# tx.net
KiCad netlist of a schematic drawn in EAGLE
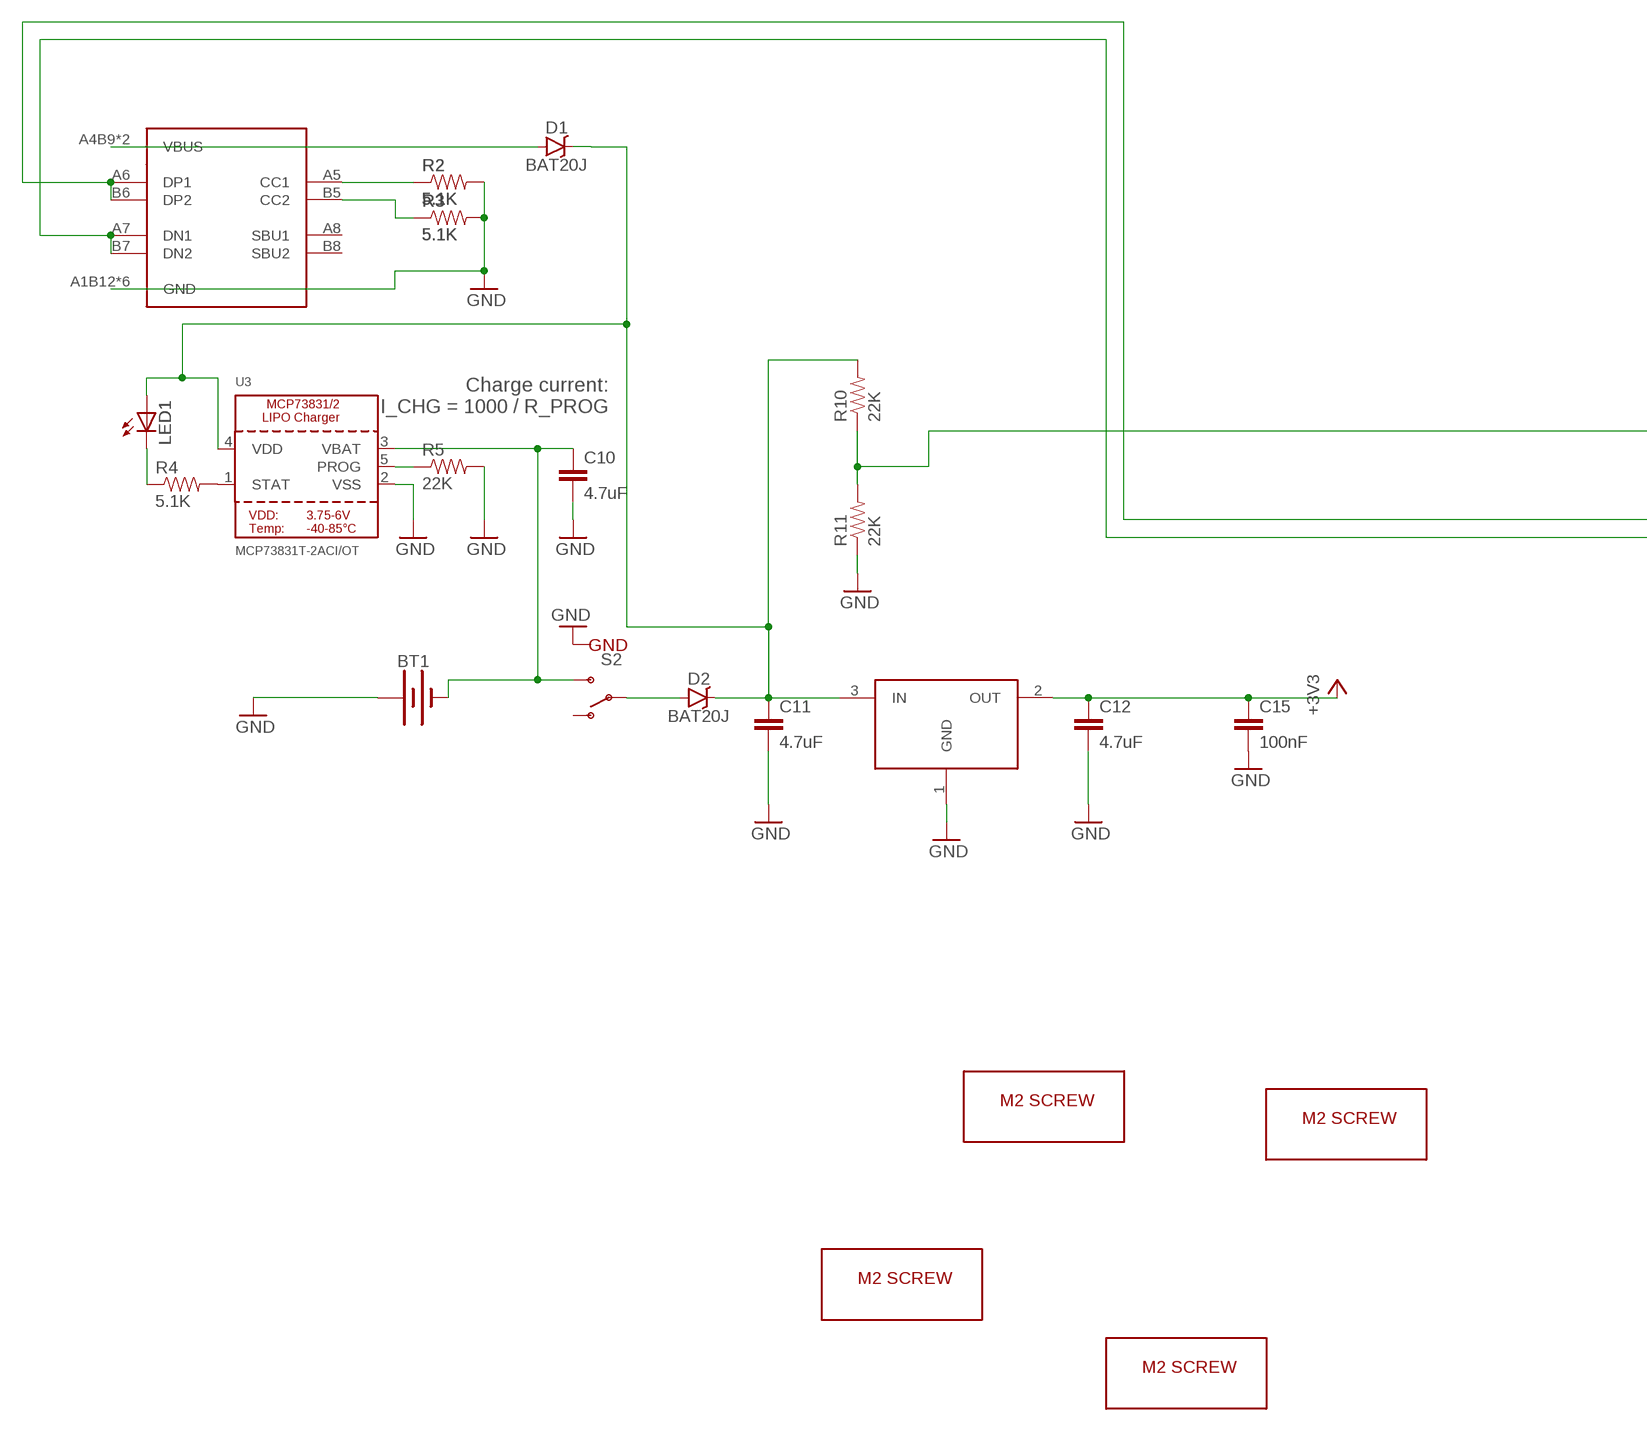
[diagram p0: schematic, sheet 1, part 1 of 2]
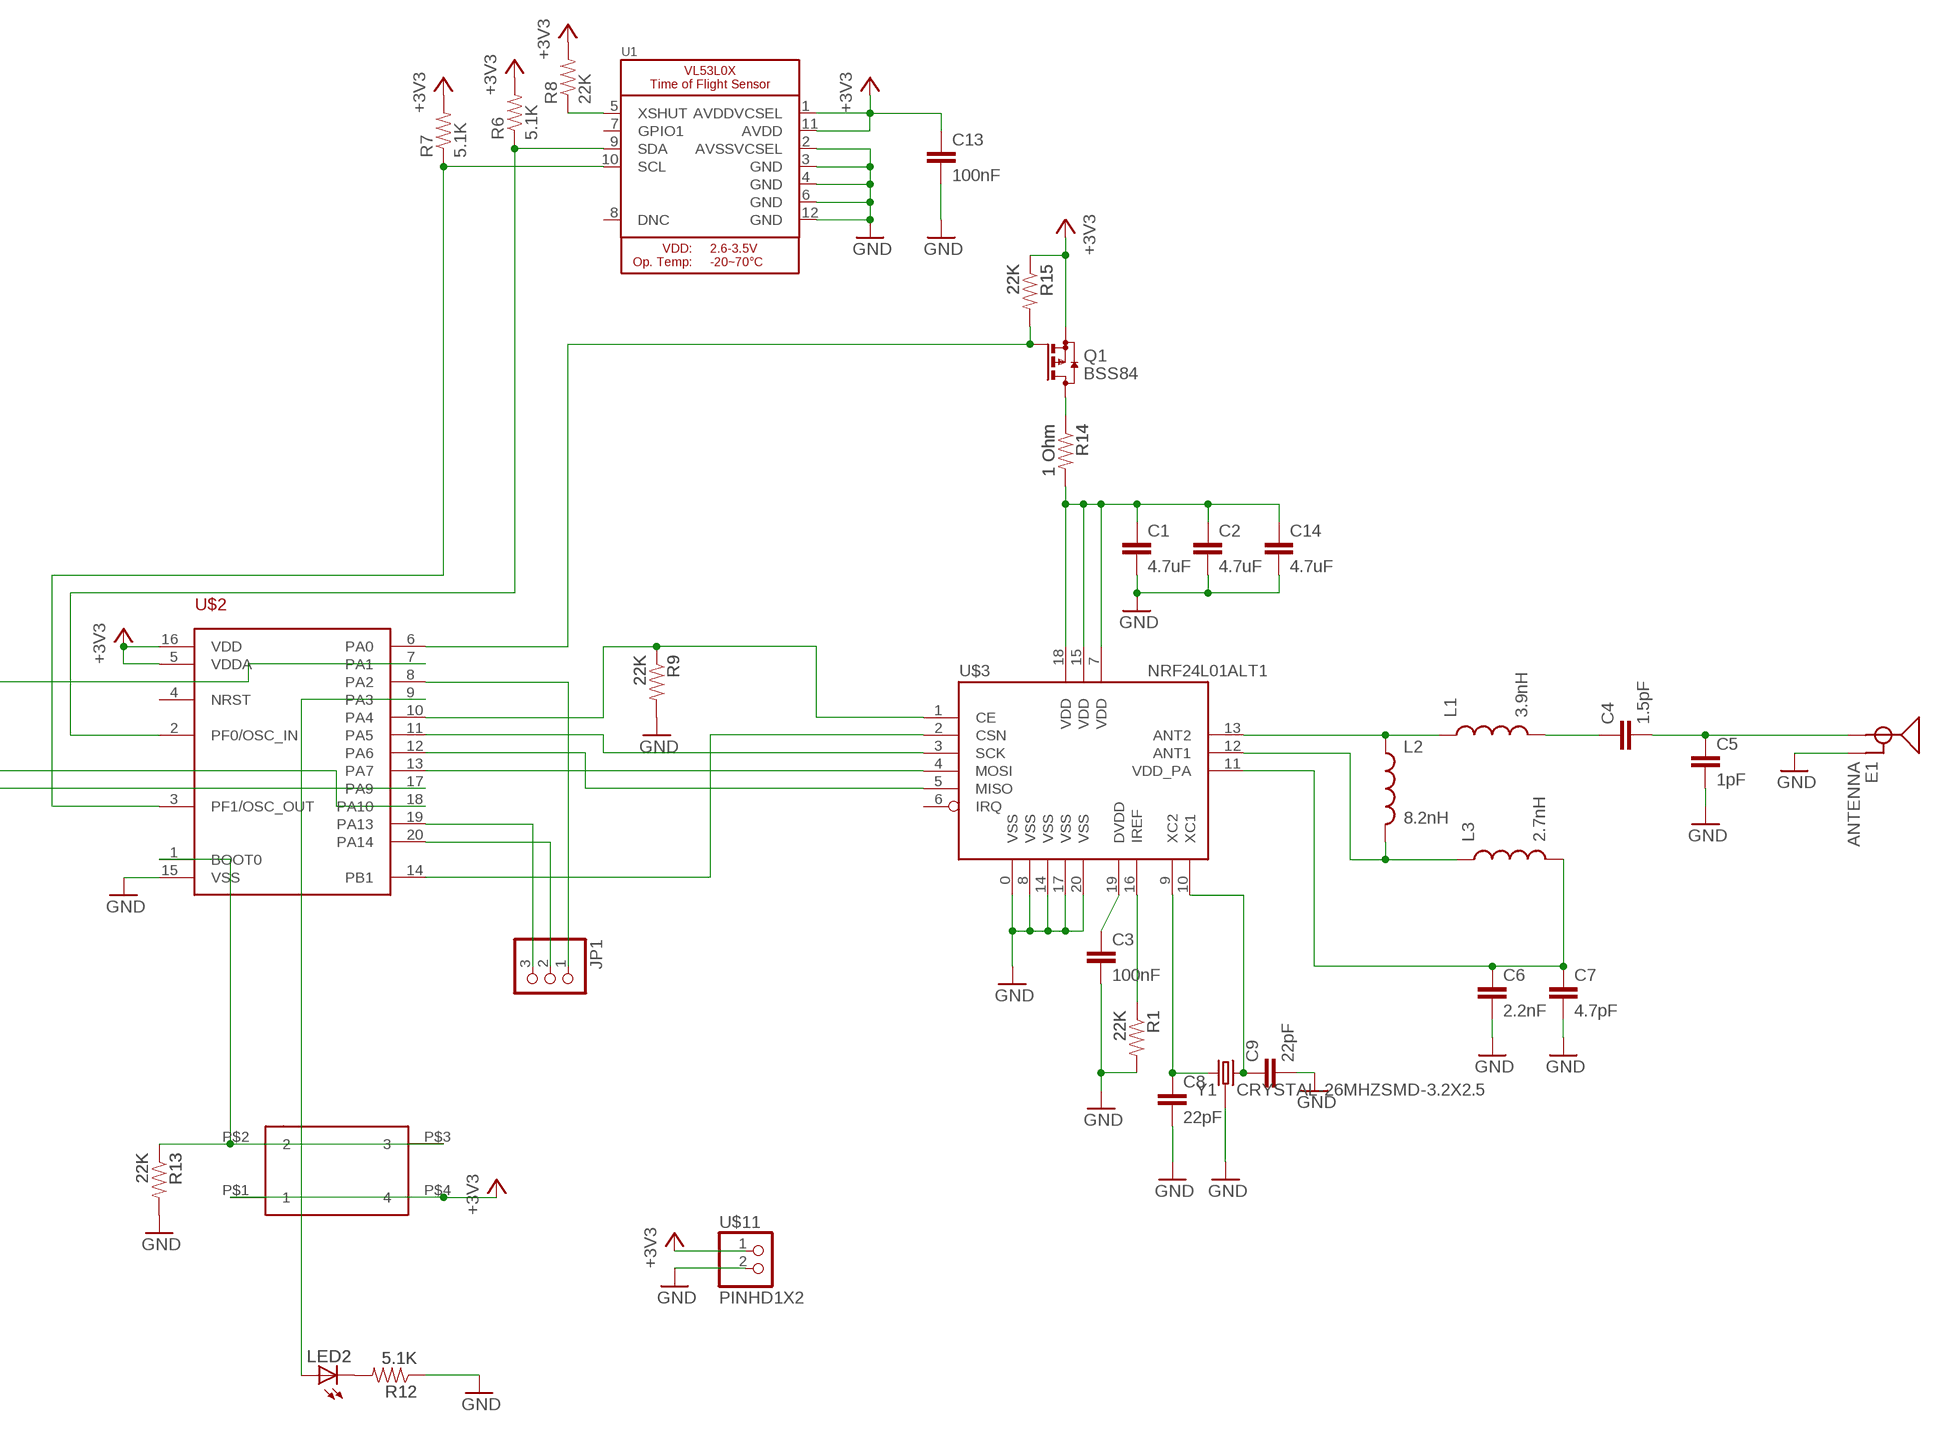
[diagram p1: schematic, sheet 1, part 2 of 2]

(export (version "E")
  (design (tool "Eeschema 10.0.6"))
  (components
    (comp (ref "BT1")
      (value "TX_SPARKFUN-BATTERIES_BATTERY-24.5MM_PTH")
      (footprint "eagle-import:TX_SPARKFUN-BATTERIES_BATTCON_24.5MM_PTH")
      (libsource (lib "eagle-import") (part "TX_SPARKFUN-BATTERIES_BATTERY-24.5MM_PTH"))
    )
    (comp (ref "C1")
      (value "4.7uF")
      (footprint "eagle-import:0805")
      (libsource (lib "eagle-import") (part "clock_CAP0805"))
    )
    (comp (ref "C2")
      (value "4.7uF")
      (footprint "eagle-import:0805")
      (libsource (lib "eagle-import") (part "clock_CAP0805"))
    )
    (comp (ref "C3")
      (value "100nF")
      (footprint "eagle-import:0805")
      (libsource (lib "eagle-import") (part "clock_CAP0805"))
    )
    (comp (ref "C4")
      (value "1.5pF")
      (footprint "eagle-import:0805")
      (libsource (lib "eagle-import") (part "clock_CAP0805"))
    )
    (comp (ref "C5")
      (value "1pF")
      (footprint "eagle-import:0805")
      (libsource (lib "eagle-import") (part "clock_CAP0805"))
    )
    (comp (ref "C6")
      (value "2.2nF")
      (footprint "eagle-import:0805")
      (libsource (lib "eagle-import") (part "clock_CAP0805"))
    )
    (comp (ref "C7")
      (value "4.7pF")
      (footprint "eagle-import:0805")
      (libsource (lib "eagle-import") (part "clock_CAP0805"))
    )
    (comp (ref "C8")
      (value "22pF")
      (footprint "eagle-import:0805")
      (libsource (lib "eagle-import") (part "clock_CAP0805"))
    )
    (comp (ref "C9")
      (value "22pF")
      (footprint "eagle-import:0805")
      (libsource (lib "eagle-import") (part "clock_CAP0805"))
    )
    (comp (ref "C10")
      (value "4.7uF")
      (footprint "eagle-import:0805")
      (libsource (lib "eagle-import") (part "CAP0805"))
    )
    (comp (ref "C11")
      (value "4.7uF")
      (footprint "eagle-import:0805")
      (libsource (lib "eagle-import") (part "clock_CAP0805"))
    )
    (comp (ref "C12")
      (value "4.7uF")
      (footprint "eagle-import:0805")
      (libsource (lib "eagle-import") (part "clock_CAP0805"))
    )
    (comp (ref "C13")
      (value "100nF")
      (footprint "eagle-import:0805")
      (libsource (lib "eagle-import") (part "clock_CAP0805"))
    )
    (comp (ref "C14")
      (value "4.7uF")
      (footprint "eagle-import:0805")
      (libsource (lib "eagle-import") (part "clock_CAP0805"))
    )
    (comp (ref "C15")
      (value "100nF")
      (footprint "eagle-import:0805")
      (libsource (lib "eagle-import") (part "clock_CAP0805"))
    )
    (comp (ref "D1")
      (value "BAT20J")
      (footprint "eagle-import:SOD-323")
      (libsource (lib "eagle-import") (part "DIODE-SCHOTTKY-BAT20J"))
    )
    (comp (ref "D2")
      (value "BAT20J")
      (footprint "eagle-import:SOD-323")
      (libsource (lib "eagle-import") (part "DIODE-SCHOTTKY-BAT20J"))
    )
    (comp (ref "E1")
      (value "ANTENNA")
      (footprint "eagle-import:TRACE_ANTENNA_2.4GHZ_25.7MM_TUNED")
      (libsource (lib "eagle-import") (part "ANTENNATRACE-TUNED"))
    )
    (comp (ref "JP1")
      (value "PINHD-1X3CB")
      (footprint "eagle-import:1X03-CLEANBIG")
      (libsource (lib "eagle-import") (part "PINHD-1X3CB"))
    )
    (comp (ref "L1")
      (value "3.9nH")
      (footprint "eagle-import:0805")
      (libsource (lib "eagle-import") (part "INDUCTOR0805"))
    )
    (comp (ref "L2")
      (value "8.2nH")
      (footprint "eagle-import:0805")
      (libsource (lib "eagle-import") (part "INDUCTOR0805"))
    )
    (comp (ref "L3")
      (value "2.7nH")
      (footprint "eagle-import:0805")
      (libsource (lib "eagle-import") (part "INDUCTOR0805"))
    )
    (comp (ref "LED1")
      (value "LEDCHIP-LED0805")
      (footprint "eagle-import:CHIP-LED0805")
      (libsource (lib "eagle-import") (part "LEDCHIP-LED0805"))
    )
    (comp (ref "LED2")
      (value "LEDCHIP-LED0805")
      (footprint "eagle-import:CHIP-LED0805")
      (libsource (lib "eagle-import") (part "LEDCHIP-LED0805"))
    )
    (comp (ref "Q1")
      (value "BSS84")
      (footprint "eagle-import:SOT23")
      (libsource (lib "eagle-import") (part "BSS84"))
    )
    (comp (ref "R1")
      (value "22K")
      (footprint "eagle-import:0805")
      (libsource (lib "eagle-import") (part "joyAnalog_RESISTOR0805-RES"))
    )
    (comp (ref "R2")
      (value "5.1K")
      (footprint "eagle-import:0805")
      (libsource (lib "eagle-import") (part "joyAnalog_RESISTOR0805-RES"))
    )
    (comp (ref "R3")
      (value "5.1K")
      (footprint "eagle-import:0805")
      (libsource (lib "eagle-import") (part "joyAnalog_RESISTOR0805-RES"))
    )
    (comp (ref "R4")
      (value "5.1K")
      (footprint "eagle-import:0805")
      (libsource (lib "eagle-import") (part "RESISTOR0805-RES"))
    )
    (comp (ref "R5")
      (value "22K")
      (footprint "eagle-import:0805")
      (libsource (lib "eagle-import") (part "RESISTOR0805-RES"))
    )
    (comp (ref "R6")
      (value "5.1K")
      (footprint "eagle-import:0805")
      (libsource (lib "eagle-import") (part "RESISTOR0805-RES"))
    )
    (comp (ref "R7")
      (value "5.1K")
      (footprint "eagle-import:0805")
      (libsource (lib "eagle-import") (part "RESISTOR0805-RES"))
    )
    (comp (ref "R8")
      (value "22K")
      (footprint "eagle-import:0805")
      (libsource (lib "eagle-import") (part "RESISTOR0805-RES"))
    )
    (comp (ref "R9")
      (value "22K")
      (footprint "eagle-import:0805")
      (libsource (lib "eagle-import") (part "joyAnalog_RESISTOR0805-RES"))
    )
    (comp (ref "R10")
      (value "22K")
      (footprint "eagle-import:0805")
      (libsource (lib "eagle-import") (part "RESISTOR0805-RES"))
    )
    (comp (ref "R11")
      (value "22K")
      (footprint "eagle-import:0805")
      (libsource (lib "eagle-import") (part "RESISTOR0805-RES"))
    )
    (comp (ref "R12")
      (value "5.1K")
      (footprint "eagle-import:0805")
      (libsource (lib "eagle-import") (part "joyAnalog_RESISTOR0805-RES"))
    )
    (comp (ref "R13")
      (value "22K")
      (footprint "eagle-import:0805")
      (libsource (lib "eagle-import") (part "joyAnalog_RESISTOR0805-RES"))
    )
    (comp (ref "R14")
      (value "1 Ohm")
      (footprint "eagle-import:0805")
      (libsource (lib "eagle-import") (part "joyAnalog_RESISTOR0805-RES"))
    )
    (comp (ref "R15")
      (value "22K")
      (footprint "eagle-import:0805")
      (libsource (lib "eagle-import") (part "joyAnalog_RESISTOR0805-RES"))
    )
    (comp (ref "S2")
      (value "SWITCH-SPDTTDFGDFG")
      (footprint "eagle-import:SWITCH-SPST-SMD-A")
      (libsource (lib "eagle-import") (part "SWITCH-SPDTTDFGDFG"))
    )
    (comp (ref "U$1")
      (value "M2_SCREW_DEV")
      (footprint "eagle-import:M2_SCREW_FOOT")
      (libsource (lib "eagle-import") (part "M2_SCREW_DEV"))
    )
    (comp (ref "U$2")
      (value "STM32F030F4")
      (footprint "eagle-import:TSSOP20")
      (libsource (lib "eagle-import") (part "STM32F030F4"))
    )
    (comp (ref "U$3")
      (value "NRF24L01ALT1")
      (footprint "eagle-import:QFN20_ALT1")
      (libsource (lib "eagle-import") (part "NRF24L01ALT1"))
    )
    (comp (ref "U$4")
      (value "USBC_16P")
      (footprint "eagle-import:USBC_16P_FOOT")
      (libsource (lib "eagle-import") (part "USBC_16P"))
    )
    (comp (ref "U$9")
      (value "XC6206_DEV")
      (footprint "eagle-import:SOT23R_INFINEON")
      (libsource (lib "eagle-import") (part "XC6206_DEV"))
    )
    (comp (ref "U$10")
      (value "324_SW324_SWITCH_FOOT_HOLE")
      (footprint "eagle-import:342_SWICH_FOOT_HOLE")
      (libsource (lib "eagle-import") (part "324_SW324_SWITCH_FOOT_HOLE"))
    )
    (comp (ref "U$11")
      (value "PINHD1X2")
      (footprint "eagle-import:1X02")
      (libsource (lib "eagle-import") (part "PINHD1X2"))
    )
    (comp (ref "U$12")
      (value "M2_SCREW_DEV")
      (footprint "eagle-import:M2_SCREW_FOOT")
      (libsource (lib "eagle-import") (part "M2_SCREW_DEV"))
    )
    (comp (ref "U$13")
      (value "M2_SCREW_DEV")
      (footprint "eagle-import:M2_SCREW_FOOT")
      (libsource (lib "eagle-import") (part "M2_SCREW_DEV"))
    )
    (comp (ref "U$14")
      (value "M2_SCREW_DEV")
      (footprint "eagle-import:M2_SCREW_FOOT")
      (libsource (lib "eagle-import") (part "M2_SCREW_DEV"))
    )
    (comp (ref "U1")
      (value "VL53L0X")
      (footprint "eagle-import:LGA12_ST")
      (libsource (lib "eagle-import") (part "VL53L0X"))
    )
    (comp (ref "U3")
      (value "MCP73831T-2ACI/OT")
      (footprint "eagle-import:SOT23-5")
      (libsource (lib "eagle-import") (part "MCP73831/2"))
    )
    (comp (ref "Y1")
      (value "CRYSTAL-26MHZSMD-3.2X2.5")
      (footprint "eagle-import:CRYSTAL-SMD-3.2X2.5MM")
      (libsource (lib "eagle-import") (part "CRYSTAL-26MHZSMD-3.2X2.5"))
    )
  )
  (nets
    (net (code "1") (name "+3V3") (class "Default")
      (node (ref "C12") (pin "1") (pinfunction "1_1") (pintype "passive"))
      (node (ref "C13") (pin "1") (pinfunction "1_1") (pintype "passive"))
      (node (ref "C15") (pin "1") (pinfunction "1_1") (pintype "passive"))
      (node (ref "Q1") (pin "2") (pinfunction "S_2") (pintype "passive"))
      (node (ref "R15") (pin "1") (pinfunction "1_1") (pintype "passive"))
      (node (ref "R6") (pin "2") (pinfunction "2_2") (pintype "passive"))
      (node (ref "R7") (pin "2") (pinfunction "2_2") (pintype "passive"))
      (node (ref "R8") (pin "2") (pinfunction "2_2") (pintype "passive"))
      (node (ref "U$10") (pin "P$1") (pinfunction "1_P$1") (pintype "bidirectional"))
      (node (ref "U$10") (pin "P$4") (pinfunction "4_P$4") (pintype "bidirectional"))
      (node (ref "U$11") (pin "1") (pinfunction "1_1") (pintype "passive"))
      (node (ref "U$2") (pin "16") (pinfunction "VDD_16") (pintype "bidirectional"))
      (node (ref "U$2") (pin "5") (pinfunction "VDDA_5") (pintype "bidirectional"))
      (node (ref "U$9") (pin "2") (pinfunction "OUT_2") (pintype "bidirectional"))
      (node (ref "U1") (pin "1") (pinfunction "AVDDVCSEL_1") (pintype "power_in"))
      (node (ref "U1") (pin "11") (pinfunction "AVDD_11") (pintype "power_in"))
    )
    (net (code "2") (name "GND") (class "Default")
      (node (ref "BT1") (pin "2") (pinfunction "+_2") (pintype "power_in"))
      (node (ref "C1") (pin "2") (pinfunction "2_2") (pintype "passive"))
      (node (ref "C10") (pin "2") (pinfunction "2_2") (pintype "passive"))
      (node (ref "C11") (pin "2") (pinfunction "2_2") (pintype "passive"))
      (node (ref "C12") (pin "2") (pinfunction "2_2") (pintype "passive"))
      (node (ref "C13") (pin "2") (pinfunction "2_2") (pintype "passive"))
      (node (ref "C14") (pin "2") (pinfunction "2_2") (pintype "passive"))
      (node (ref "C15") (pin "2") (pinfunction "2_2") (pintype "passive"))
      (node (ref "C2") (pin "2") (pinfunction "2_2") (pintype "passive"))
      (node (ref "C3") (pin "2") (pinfunction "2_2") (pintype "passive"))
      (node (ref "C5") (pin "2") (pinfunction "2_2") (pintype "passive"))
      (node (ref "C6") (pin "2") (pinfunction "2_2") (pintype "passive"))
      (node (ref "C7") (pin "2") (pinfunction "2_2") (pintype "passive"))
      (node (ref "C8") (pin "2") (pinfunction "2_2") (pintype "passive"))
      (node (ref "C9") (pin "2") (pinfunction "2_2") (pintype "passive"))
      (node (ref "E1") (pin "GND") (pinfunction "GND_GND") (pintype "bidirectional"))
      (node (ref "E1") (pin "GND2") (pinfunction "GND_GND2") (pintype "bidirectional"))
      (node (ref "R1") (pin "2") (pinfunction "2_2") (pintype "passive"))
      (node (ref "R11") (pin "1") (pinfunction "1_1") (pintype "passive"))
      (node (ref "R12") (pin "1") (pinfunction "1_1") (pintype "passive"))
      (node (ref "R13") (pin "2") (pinfunction "2_2") (pintype "passive"))
      (node (ref "R2") (pin "2") (pinfunction "2_2") (pintype "passive"))
      (node (ref "R3") (pin "2") (pinfunction "2_2") (pintype "passive"))
      (node (ref "R5") (pin "2") (pinfunction "2_2") (pintype "passive"))
      (node (ref "R9") (pin "2") (pinfunction "2_2") (pintype "passive"))
      (node (ref "S2") (pin "G1") (pinfunction "GND_G1") (pintype "passive"))
      (node (ref "S2") (pin "G2") (pinfunction "GND_G2") (pintype "passive"))
      (node (ref "S2") (pin "G3") (pinfunction "GND_G3") (pintype "passive"))
      (node (ref "S2") (pin "G4") (pinfunction "GND_G4") (pintype "passive"))
      (node (ref "U$11") (pin "2") (pinfunction "2_2") (pintype "passive"))
      (node (ref "U$2") (pin "15") (pinfunction "VSS_15") (pintype "bidirectional"))
      (node (ref "U$3") (pin "0") (pinfunction "VSS_0") (pintype "power_in"))
      (node (ref "U$3") (pin "14") (pinfunction "VSS_14") (pintype "power_in"))
      (node (ref "U$3") (pin "17") (pinfunction "VSS_17") (pintype "power_in"))
      (node (ref "U$3") (pin "20") (pinfunction "VSS_20") (pintype "power_in"))
      (node (ref "U$3") (pin "8") (pinfunction "VSS_8") (pintype "power_in"))
      (node (ref "U$4") (pin "A1B12") (pinfunction "GND_A1B12") (pintype "bidirectional"))
      (node (ref "U$4") (pin "B11A12") (pinfunction "GND_B11A12") (pintype "bidirectional"))
      (node (ref "U$4") (pin "P$13") (pinfunction "GND_P$13") (pintype "bidirectional"))
      (node (ref "U$4") (pin "P$14") (pinfunction "GND_P$14") (pintype "bidirectional"))
      (node (ref "U$4") (pin "P$15") (pinfunction "GND_P$15") (pintype "bidirectional"))
      (node (ref "U$4") (pin "P$16") (pinfunction "GND_P$16") (pintype "bidirectional"))
      (node (ref "U$9") (pin "1") (pinfunction "GND_1") (pintype "bidirectional"))
      (node (ref "U1") (pin "12") (pinfunction "GND_12") (pintype "power_in"))
      (node (ref "U1") (pin "2") (pinfunction "AVSSVCSEL_2") (pintype "power_in"))
      (node (ref "U1") (pin "3") (pinfunction "GND_3") (pintype "power_in"))
      (node (ref "U1") (pin "4") (pinfunction "GND_4") (pintype "power_in"))
      (node (ref "U1") (pin "6") (pinfunction "GND_6") (pintype "power_in"))
      (node (ref "U3") (pin "2") (pinfunction "VSS_2") (pintype "power_in"))
      (node (ref "Y1") (pin "2") (pinfunction "3_2") (pintype "passive"))
      (node (ref "Y1") (pin "4") (pinfunction "3_4") (pintype "passive"))
    )
    (net (code "3") (name "Net-(BT1--)") (class "Default")
      (node (ref "BT1") (pin "1") (pinfunction "-_1") (pintype "power_in"))
      (node (ref "C10") (pin "1") (pinfunction "1_1") (pintype "passive"))
      (node (ref "S2") (pin "3") (pinfunction "S_3") (pintype "passive"))
      (node (ref "U3") (pin "3") (pinfunction "VBAT_3") (pintype "power_in"))
    )
    (net (code "4") (name "Net-(C1-Pad1)") (class "Default")
      (node (ref "C1") (pin "1") (pinfunction "1_1") (pintype "passive"))
      (node (ref "C14") (pin "1") (pinfunction "1_1") (pintype "passive"))
      (node (ref "C2") (pin "1") (pinfunction "1_1") (pintype "passive"))
      (node (ref "R14") (pin "2") (pinfunction "2_2") (pintype "passive"))
      (node (ref "U$3") (pin "15") (pinfunction "VDD_15") (pintype "power_in"))
      (node (ref "U$3") (pin "18") (pinfunction "VDD_18") (pintype "power_in"))
      (node (ref "U$3") (pin "7") (pinfunction "VDD_7") (pintype "power_in"))
    )
    (net (code "5") (name "Net-(C4-Pad1)") (class "Default")
      (node (ref "C4") (pin "1") (pinfunction "1_1") (pintype "passive"))
      (node (ref "L1") (pin "2") (pinfunction "2_2") (pintype "passive"))
    )
    (net (code "6") (name "Net-(D1-PadA)") (class "Default")
      (node (ref "D1") (pin "A") (pinfunction "A_A") (pintype "passive"))
      (node (ref "U$4") (pin "A4B9") (pinfunction "VBUS_A4B9") (pintype "bidirectional"))
      (node (ref "U$4") (pin "B4A9") (pinfunction "VBUS_B4A9") (pintype "bidirectional"))
    )
    (net (code "7") (name "Net-(E1-SIGNAL)") (class "Default")
      (node (ref "C4") (pin "2") (pinfunction "2_2") (pintype "passive"))
      (node (ref "C5") (pin "1") (pinfunction "1_1") (pintype "passive"))
      (node (ref "E1") (pin "ANT") (pinfunction "SIGNAL_ANT") (pintype "bidirectional"))
    )
    (net (code "8") (name "Net-(LED1-PadC)") (class "Default")
      (node (ref "LED1") (pin "C") (pinfunction "C_C") (pintype "passive"))
      (node (ref "R4") (pin "1") (pinfunction "1_1") (pintype "passive"))
    )
    (net (code "9") (name "Net-(LED2-PadC)") (class "Default")
      (node (ref "LED2") (pin "C") (pinfunction "C_C") (pintype "passive"))
      (node (ref "R12") (pin "2") (pinfunction "2_2") (pintype "passive"))
    )
    (net (code "10") (name "Net-(Q1-D)") (class "Default")
      (node (ref "Q1") (pin "3") (pinfunction "D_3") (pintype "passive"))
      (node (ref "R14") (pin "1") (pinfunction "1_1") (pintype "passive"))
    )
    (net (code "11") (name "Net-(Q1-G)") (class "Default")
      (node (ref "Q1") (pin "1") (pinfunction "G_1") (pintype "passive"))
      (node (ref "R15") (pin "2") (pinfunction "2_2") (pintype "passive"))
      (node (ref "U$2") (pin "6") (pinfunction "PA0_6") (pintype "bidirectional"))
    )
    (net (code "12") (name "Net-(S2-P)") (class "Default")
      (node (ref "D2") (pin "A") (pinfunction "A_A") (pintype "passive"))
      (node (ref "S2") (pin "2") (pinfunction "P_2") (pintype "passive"))
    )
    (net (code "13") (name "Net-(U$2-PA1)") (class "Default")
      (node (ref "R10") (pin "1") (pinfunction "1_1") (pintype "passive"))
      (node (ref "R11") (pin "2") (pinfunction "2_2") (pintype "passive"))
      (node (ref "U$2") (pin "7") (pinfunction "PA1_7") (pintype "bidirectional"))
    )
    (net (code "14") (name "Net-(U$2-PA2)") (class "Default")
      (node (ref "JP1") (pin "1") (pinfunction "1_1") (pintype "passive"))
      (node (ref "U$2") (pin "8") (pinfunction "PA2_8") (pintype "bidirectional"))
    )
    (net (code "15") (name "Net-(U$2-PA3)") (class "Default")
      (node (ref "LED2") (pin "A") (pinfunction "A_A") (pintype "passive"))
      (node (ref "U$2") (pin "9") (pinfunction "PA3_9") (pintype "bidirectional"))
    )
    (net (code "16") (name "Net-(U$2-PA4)") (class "Default")
      (node (ref "R9") (pin "1") (pinfunction "1_1") (pintype "passive"))
      (node (ref "U$2") (pin "10") (pinfunction "PA4_10") (pintype "bidirectional"))
      (node (ref "U$3") (pin "1") (pinfunction "CE_1") (pintype "input"))
    )
    (net (code "17") (name "Net-(U$2-PA5)") (class "Default")
      (node (ref "U$2") (pin "11") (pinfunction "PA5_11") (pintype "bidirectional"))
      (node (ref "U$3") (pin "3") (pinfunction "SCK_3") (pintype "input"))
    )
    (net (code "18") (name "Net-(U$2-PA6)") (class "Default")
      (node (ref "U$2") (pin "12") (pinfunction "PA6_12") (pintype "bidirectional"))
      (node (ref "U$3") (pin "5") (pinfunction "MISO_5") (pintype "output"))
    )
    (net (code "19") (name "Net-(U$2-PA7)") (class "Default")
      (node (ref "U$2") (pin "13") (pinfunction "PA7_13") (pintype "bidirectional"))
      (node (ref "U$3") (pin "4") (pinfunction "MOSI_4") (pintype "input"))
    )
    (net (code "20") (name "Net-(U$2-PA9)") (class "Default")
      (node (ref "U$2") (pin "17") (pinfunction "PA9_17") (pintype "bidirectional"))
      (node (ref "U$4") (pin "A7") (pinfunction "DN1_A7") (pintype "bidirectional"))
      (node (ref "U$4") (pin "B7") (pinfunction "DN2_B7") (pintype "bidirectional"))
    )
    (net (code "21") (name "Net-(U$2-PA10)") (class "Default")
      (node (ref "U$2") (pin "18") (pinfunction "PA10_18") (pintype "bidirectional"))
      (node (ref "U$4") (pin "A6") (pinfunction "DP1_A6") (pintype "bidirectional"))
      (node (ref "U$4") (pin "B6") (pinfunction "DP2_B6") (pintype "bidirectional"))
    )
    (net (code "22") (name "Net-(U$2-PA13)") (class "Default")
      (node (ref "JP1") (pin "3") (pinfunction "3_3") (pintype "passive"))
      (node (ref "U$2") (pin "19") (pinfunction "PA13_19") (pintype "bidirectional"))
    )
    (net (code "23") (name "Net-(U$2-PA14)") (class "Default")
      (node (ref "JP1") (pin "2") (pinfunction "2_2") (pintype "passive"))
      (node (ref "U$2") (pin "20") (pinfunction "PA14_20") (pintype "bidirectional"))
    )
    (net (code "24") (name "Net-(U$2-PB1)") (class "Default")
      (node (ref "U$2") (pin "14") (pinfunction "PB1_14") (pintype "bidirectional"))
      (node (ref "U$3") (pin "2") (pinfunction "CSN_2") (pintype "input"))
    )
    (net (code "25") (name "Net-(U$2-PF0{slash}OSC_IN)") (class "Default")
      (node (ref "R6") (pin "1") (pinfunction "1_1") (pintype "passive"))
      (node (ref "U$2") (pin "2") (pinfunction "PF0/OSC_IN_2") (pintype "bidirectional"))
      (node (ref "U1") (pin "9") (pinfunction "SDA_9") (pintype "open_collector"))
    )
    (net (code "26") (name "Net-(U$2-PF1{slash}OSC_OUT)") (class "Default")
      (node (ref "R7") (pin "1") (pinfunction "1_1") (pintype "passive"))
      (node (ref "U$2") (pin "3") (pinfunction "PF1/OSC_OUT_3") (pintype "bidirectional"))
      (node (ref "U1") (pin "10") (pinfunction "SCL_10") (pintype "open_collector"))
    )
    (net (code "27") (name "Net-(U$3-ANT1)") (class "Default")
      (node (ref "L2") (pin "2") (pinfunction "2_2") (pintype "passive"))
      (node (ref "L3") (pin "1") (pinfunction "1_1") (pintype "passive"))
      (node (ref "U$3") (pin "12") (pinfunction "ANT1_12") (pintype "output"))
    )
    (net (code "28") (name "Net-(U$3-ANT2)") (class "Default")
      (node (ref "L1") (pin "1") (pinfunction "1_1") (pintype "passive"))
      (node (ref "L2") (pin "1") (pinfunction "1_1") (pintype "passive"))
      (node (ref "U$3") (pin "13") (pinfunction "ANT2_13") (pintype "output"))
    )
    (net (code "29") (name "Net-(U$3-DVDD)") (class "Default")
      (node (ref "C3") (pin "1") (pinfunction "1_1") (pintype "passive"))
      (node (ref "U$3") (pin "19") (pinfunction "DVDD_19") (pintype "power_in"))
    )
    (net (code "30") (name "Net-(U$3-IREF)") (class "Default")
      (node (ref "R1") (pin "1") (pinfunction "1_1") (pintype "passive"))
      (node (ref "U$3") (pin "16") (pinfunction "IREF_16") (pintype "input"))
    )
    (net (code "31") (name "Net-(U$3-VDD_PA)") (class "Default")
      (node (ref "C6") (pin "1") (pinfunction "1_1") (pintype "passive"))
      (node (ref "C7") (pin "1") (pinfunction "1_1") (pintype "passive"))
      (node (ref "L3") (pin "2") (pinfunction "2_2") (pintype "passive"))
      (node (ref "U$3") (pin "11") (pinfunction "VDD_PA_11") (pintype "power_in"))
    )
    (net (code "32") (name "Net-(U$3-XC1)") (class "Default")
      (node (ref "C9") (pin "1") (pinfunction "1_1") (pintype "passive"))
      (node (ref "U$3") (pin "10") (pinfunction "XC1_10") (pintype "input"))
      (node (ref "Y1") (pin "3") (pinfunction "2_3") (pintype "passive"))
    )
    (net (code "33") (name "Net-(U$3-XC2)") (class "Default")
      (node (ref "C8") (pin "1") (pinfunction "1_1") (pintype "passive"))
      (node (ref "U$3") (pin "9") (pinfunction "XC2_9") (pintype "input"))
      (node (ref "Y1") (pin "1") (pinfunction "1_1") (pintype "passive"))
    )
    (net (code "34") (name "Net-(U$4-CC1)") (class "Default")
      (node (ref "R2") (pin "1") (pinfunction "1_1") (pintype "passive"))
      (node (ref "U$4") (pin "A5") (pinfunction "CC1_A5") (pintype "bidirectional"))
    )
    (net (code "35") (name "Net-(U$4-CC2)") (class "Default")
      (node (ref "R3") (pin "1") (pinfunction "1_1") (pintype "passive"))
      (node (ref "U$4") (pin "B5") (pinfunction "CC2_B5") (pintype "bidirectional"))
    )
    (net (code "36") (name "Net-(U$9-IN)") (class "Default")
      (node (ref "C11") (pin "1") (pinfunction "1_1") (pintype "passive"))
      (node (ref "D1") (pin "C") (pinfunction "C_C") (pintype "passive"))
      (node (ref "D2") (pin "C") (pinfunction "C_C") (pintype "passive"))
      (node (ref "LED1") (pin "A") (pinfunction "A_A") (pintype "passive"))
      (node (ref "R10") (pin "2") (pinfunction "2_2") (pintype "passive"))
      (node (ref "U$9") (pin "3") (pinfunction "IN_3") (pintype "bidirectional"))
      (node (ref "U3") (pin "4") (pinfunction "VDD_4") (pintype "power_in"))
    )
    (net (code "37") (name "Net-(U$10-2)") (class "Default")
      (node (ref "R13") (pin "1") (pinfunction "1_1") (pintype "passive"))
      (node (ref "U$10") (pin "P$2") (pinfunction "2_P$2") (pintype "bidirectional"))
      (node (ref "U$10") (pin "P$3") (pinfunction "3_P$3") (pintype "bidirectional"))
      (node (ref "U$2") (pin "1") (pinfunction "BOOT0_1") (pintype "bidirectional"))
    )
    (net (code "38") (name "Net-(U1-XSHUT)") (class "Default")
      (node (ref "R8") (pin "1") (pinfunction "1_1") (pintype "passive"))
      (node (ref "U1") (pin "5") (pinfunction "XSHUT_5") (pintype "input"))
    )
    (net (code "39") (name "Net-(U3-PROG)") (class "Default")
      (node (ref "R5") (pin "1") (pinfunction "1_1") (pintype "passive"))
      (node (ref "U3") (pin "5") (pinfunction "PROG_5") (pintype "input"))
    )
    (net (code "40") (name "Net-(U3-STAT)") (class "Default")
      (node (ref "R4") (pin "2") (pinfunction "2_2") (pintype "passive"))
      (node (ref "U3") (pin "1") (pinfunction "STAT_1") (pintype "output"))
    )
    (net (code "41") (name "unconnected-(S2-O-Pad1)") (class "Default")
      (node (ref "S2") (pin "1") (pinfunction "O_1") (pintype "passive"))
    )
    (net (code "42") (name "unconnected-(U$2-NRST-Pad4)") (class "Default")
      (node (ref "U$2") (pin "4") (pinfunction "NRST_4") (pintype "bidirectional"))
    )
    (net (code "43") (name "unconnected-(U$3-IRQ-Pad6)") (class "Default")
      (node (ref "U$3") (pin "6") (pinfunction "IRQ_6") (pintype "output"))
    )
    (net (code "44") (name "unconnected-(U$4-SBU1-PadA8)") (class "Default")
      (node (ref "U$4") (pin "A8") (pinfunction "SBU1_A8") (pintype "bidirectional"))
    )
    (net (code "45") (name "unconnected-(U$4-SBU2-PadB8)") (class "Default")
      (node (ref "U$4") (pin "B8") (pinfunction "SBU2_B8") (pintype "bidirectional"))
    )
    (net (code "46") (name "unconnected-(U1-DNC-Pad8)") (class "Default")
      (node (ref "U1") (pin "8") (pinfunction "DNC_8") (pintype "no_connect"))
    )
    (net (code "47") (name "unconnected-(U1-GPIO1-Pad7)") (class "Default")
      (node (ref "U1") (pin "7") (pinfunction "GPIO1_7") (pintype "output"))
    )
  )
)
